# rpi-ds17b20.net
KiCad netlist of a schematic drawn in EAGLE
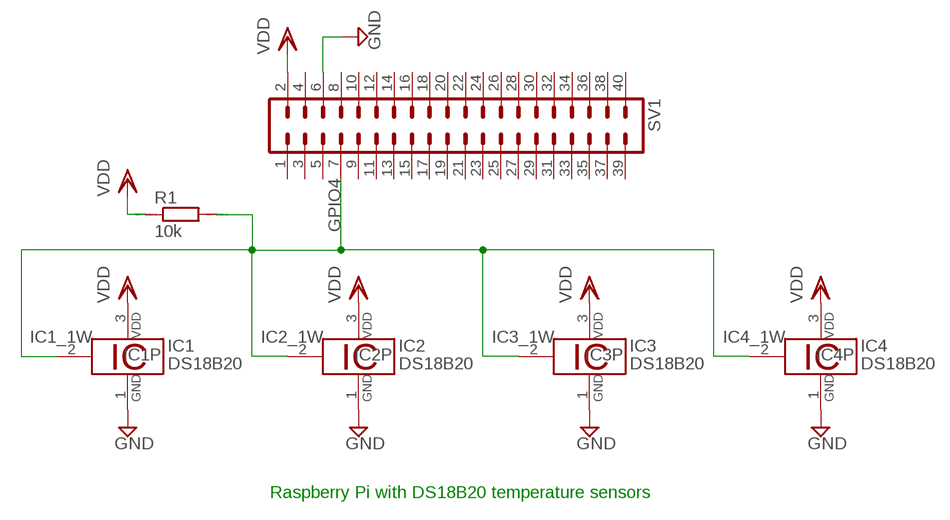
[diagram p0: schematic, sheet 1]

(export (version "E")
  (design (tool "Eeschema 10.0.6"))
  (components
    (comp (ref "IC1")
      (value "DS18B20")
      (footprint "eagle-import:TO92-")
      (libsource (lib "eagle-import") (part "DS18B20"))
    )
    (comp (ref "IC2")
      (value "DS18B20")
      (footprint "eagle-import:TO92-")
      (libsource (lib "eagle-import") (part "DS18B20"))
    )
    (comp (ref "IC3")
      (value "DS18B20")
      (footprint "eagle-import:TO92-")
      (libsource (lib "eagle-import") (part "DS18B20"))
    )
    (comp (ref "IC4")
      (value "DS18B20")
      (footprint "eagle-import:TO92-")
      (libsource (lib "eagle-import") (part "DS18B20"))
    )
    (comp (ref "R1")
      (value "10k")
      (footprint "eagle-import:0204_7")
      (libsource (lib "eagle-import") (part "R0204/7"))
    )
    (comp (ref "SV1")
      (value "MA20-2")
      (footprint "eagle-import:MA20-2")
      (libsource (lib "eagle-import") (part "MA20-2"))
    )
  )
  (nets
    (net (code "1") (name "/GPIO4") (class "Default")
      (node (ref "IC1") (pin "2") (pinfunction "1W_2") (pintype "power_in"))
      (node (ref "IC2") (pin "2") (pinfunction "1W_2") (pintype "power_in"))
      (node (ref "IC3") (pin "2") (pinfunction "1W_2") (pintype "power_in"))
      (node (ref "IC4") (pin "2") (pinfunction "1W_2") (pintype "power_in"))
      (node (ref "R1") (pin "2") (pinfunction "2_2") (pintype "passive"))
      (node (ref "SV1") (pin "7") (pinfunction "7_7") (pintype "passive"))
    )
    (net (code "2") (name "GND") (class "Default")
      (node (ref "IC1") (pin "1") (pinfunction "GND_1") (pintype "power_in"))
      (node (ref "IC2") (pin "1") (pinfunction "GND_1") (pintype "power_in"))
      (node (ref "IC3") (pin "1") (pinfunction "GND_1") (pintype "power_in"))
      (node (ref "IC4") (pin "1") (pinfunction "GND_1") (pintype "power_in"))
      (node (ref "SV1") (pin "6") (pinfunction "6_6") (pintype "passive"))
    )
    (net (code "3") (name "VDD") (class "Default")
      (node (ref "IC1") (pin "3") (pinfunction "VDD_3") (pintype "power_in"))
      (node (ref "IC2") (pin "3") (pinfunction "VDD_3") (pintype "power_in"))
      (node (ref "IC3") (pin "3") (pinfunction "VDD_3") (pintype "power_in"))
      (node (ref "IC4") (pin "3") (pinfunction "VDD_3") (pintype "power_in"))
      (node (ref "R1") (pin "1") (pinfunction "1_1") (pintype "passive"))
      (node (ref "SV1") (pin "2") (pinfunction "2_2") (pintype "passive"))
    )
    (net (code "4") (name "unconnected-(SV1-Pad1)") (class "Default")
      (node (ref "SV1") (pin "1") (pinfunction "1_1") (pintype "passive"))
    )
    (net (code "5") (name "unconnected-(SV1-Pad3)") (class "Default")
      (node (ref "SV1") (pin "3") (pinfunction "3_3") (pintype "passive"))
    )
    (net (code "6") (name "unconnected-(SV1-Pad4)") (class "Default")
      (node (ref "SV1") (pin "4") (pinfunction "4_4") (pintype "passive"))
    )
    (net (code "7") (name "unconnected-(SV1-Pad5)") (class "Default")
      (node (ref "SV1") (pin "5") (pinfunction "5_5") (pintype "passive"))
    )
    (net (code "8") (name "unconnected-(SV1-Pad8)") (class "Default")
      (node (ref "SV1") (pin "8") (pinfunction "8_8") (pintype "passive"))
    )
    (net (code "9") (name "unconnected-(SV1-Pad9)") (class "Default")
      (node (ref "SV1") (pin "9") (pinfunction "9_9") (pintype "passive"))
    )
    (net (code "10") (name "unconnected-(SV1-Pad10)") (class "Default")
      (node (ref "SV1") (pin "10") (pinfunction "10_10") (pintype "passive"))
    )
    (net (code "11") (name "unconnected-(SV1-Pad11)") (class "Default")
      (node (ref "SV1") (pin "11") (pinfunction "11_11") (pintype "passive"))
    )
    (net (code "12") (name "unconnected-(SV1-Pad12)") (class "Default")
      (node (ref "SV1") (pin "12") (pinfunction "12_12") (pintype "passive"))
    )
    (net (code "13") (name "unconnected-(SV1-Pad13)") (class "Default")
      (node (ref "SV1") (pin "13") (pinfunction "13_13") (pintype "passive"))
    )
    (net (code "14") (name "unconnected-(SV1-Pad14)") (class "Default")
      (node (ref "SV1") (pin "14") (pinfunction "14_14") (pintype "passive"))
    )
    (net (code "15") (name "unconnected-(SV1-Pad15)") (class "Default")
      (node (ref "SV1") (pin "15") (pinfunction "15_15") (pintype "passive"))
    )
    (net (code "16") (name "unconnected-(SV1-Pad16)") (class "Default")
      (node (ref "SV1") (pin "16") (pinfunction "16_16") (pintype "passive"))
    )
    (net (code "17") (name "unconnected-(SV1-Pad17)") (class "Default")
      (node (ref "SV1") (pin "17") (pinfunction "17_17") (pintype "passive"))
    )
    (net (code "18") (name "unconnected-(SV1-Pad18)") (class "Default")
      (node (ref "SV1") (pin "18") (pinfunction "18_18") (pintype "passive"))
    )
    (net (code "19") (name "unconnected-(SV1-Pad19)") (class "Default")
      (node (ref "SV1") (pin "19") (pinfunction "19_19") (pintype "passive"))
    )
    (net (code "20") (name "unconnected-(SV1-Pad20)") (class "Default")
      (node (ref "SV1") (pin "20") (pinfunction "20_20") (pintype "passive"))
    )
    (net (code "21") (name "unconnected-(SV1-Pad21)") (class "Default")
      (node (ref "SV1") (pin "21") (pinfunction "21_21") (pintype "passive"))
    )
    (net (code "22") (name "unconnected-(SV1-Pad22)") (class "Default")
      (node (ref "SV1") (pin "22") (pinfunction "22_22") (pintype "passive"))
    )
    (net (code "23") (name "unconnected-(SV1-Pad23)") (class "Default")
      (node (ref "SV1") (pin "23") (pinfunction "23_23") (pintype "passive"))
    )
    (net (code "24") (name "unconnected-(SV1-Pad24)") (class "Default")
      (node (ref "SV1") (pin "24") (pinfunction "24_24") (pintype "passive"))
    )
    (net (code "25") (name "unconnected-(SV1-Pad25)") (class "Default")
      (node (ref "SV1") (pin "25") (pinfunction "25_25") (pintype "passive"))
    )
    (net (code "26") (name "unconnected-(SV1-Pad26)") (class "Default")
      (node (ref "SV1") (pin "26") (pinfunction "26_26") (pintype "passive"))
    )
    (net (code "27") (name "unconnected-(SV1-Pad27)") (class "Default")
      (node (ref "SV1") (pin "27") (pinfunction "27_27") (pintype "passive"))
    )
    (net (code "28") (name "unconnected-(SV1-Pad28)") (class "Default")
      (node (ref "SV1") (pin "28") (pinfunction "28_28") (pintype "passive"))
    )
    (net (code "29") (name "unconnected-(SV1-Pad29)") (class "Default")
      (node (ref "SV1") (pin "29") (pinfunction "29_29") (pintype "passive"))
    )
    (net (code "30") (name "unconnected-(SV1-Pad30)") (class "Default")
      (node (ref "SV1") (pin "30") (pinfunction "30_30") (pintype "passive"))
    )
    (net (code "31") (name "unconnected-(SV1-Pad31)") (class "Default")
      (node (ref "SV1") (pin "31") (pinfunction "31_31") (pintype "passive"))
    )
    (net (code "32") (name "unconnected-(SV1-Pad32)") (class "Default")
      (node (ref "SV1") (pin "32") (pinfunction "32_32") (pintype "passive"))
    )
    (net (code "33") (name "unconnected-(SV1-Pad33)") (class "Default")
      (node (ref "SV1") (pin "33") (pinfunction "33_33") (pintype "passive"))
    )
    (net (code "34") (name "unconnected-(SV1-Pad34)") (class "Default")
      (node (ref "SV1") (pin "34") (pinfunction "34_34") (pintype "passive"))
    )
    (net (code "35") (name "unconnected-(SV1-Pad35)") (class "Default")
      (node (ref "SV1") (pin "35") (pinfunction "35_35") (pintype "passive"))
    )
    (net (code "36") (name "unconnected-(SV1-Pad36)") (class "Default")
      (node (ref "SV1") (pin "36") (pinfunction "36_36") (pintype "passive"))
    )
    (net (code "37") (name "unconnected-(SV1-Pad37)") (class "Default")
      (node (ref "SV1") (pin "37") (pinfunction "37_37") (pintype "passive"))
    )
    (net (code "38") (name "unconnected-(SV1-Pad38)") (class "Default")
      (node (ref "SV1") (pin "38") (pinfunction "38_38") (pintype "passive"))
    )
    (net (code "39") (name "unconnected-(SV1-Pad39)") (class "Default")
      (node (ref "SV1") (pin "39") (pinfunction "39_39") (pintype "passive"))
    )
    (net (code "40") (name "unconnected-(SV1-Pad40)") (class "Default")
      (node (ref "SV1") (pin "40") (pinfunction "40_40") (pintype "passive"))
    )
  )
)
